# LilyPixel.net
KiCad netlist of a schematic drawn in EAGLE
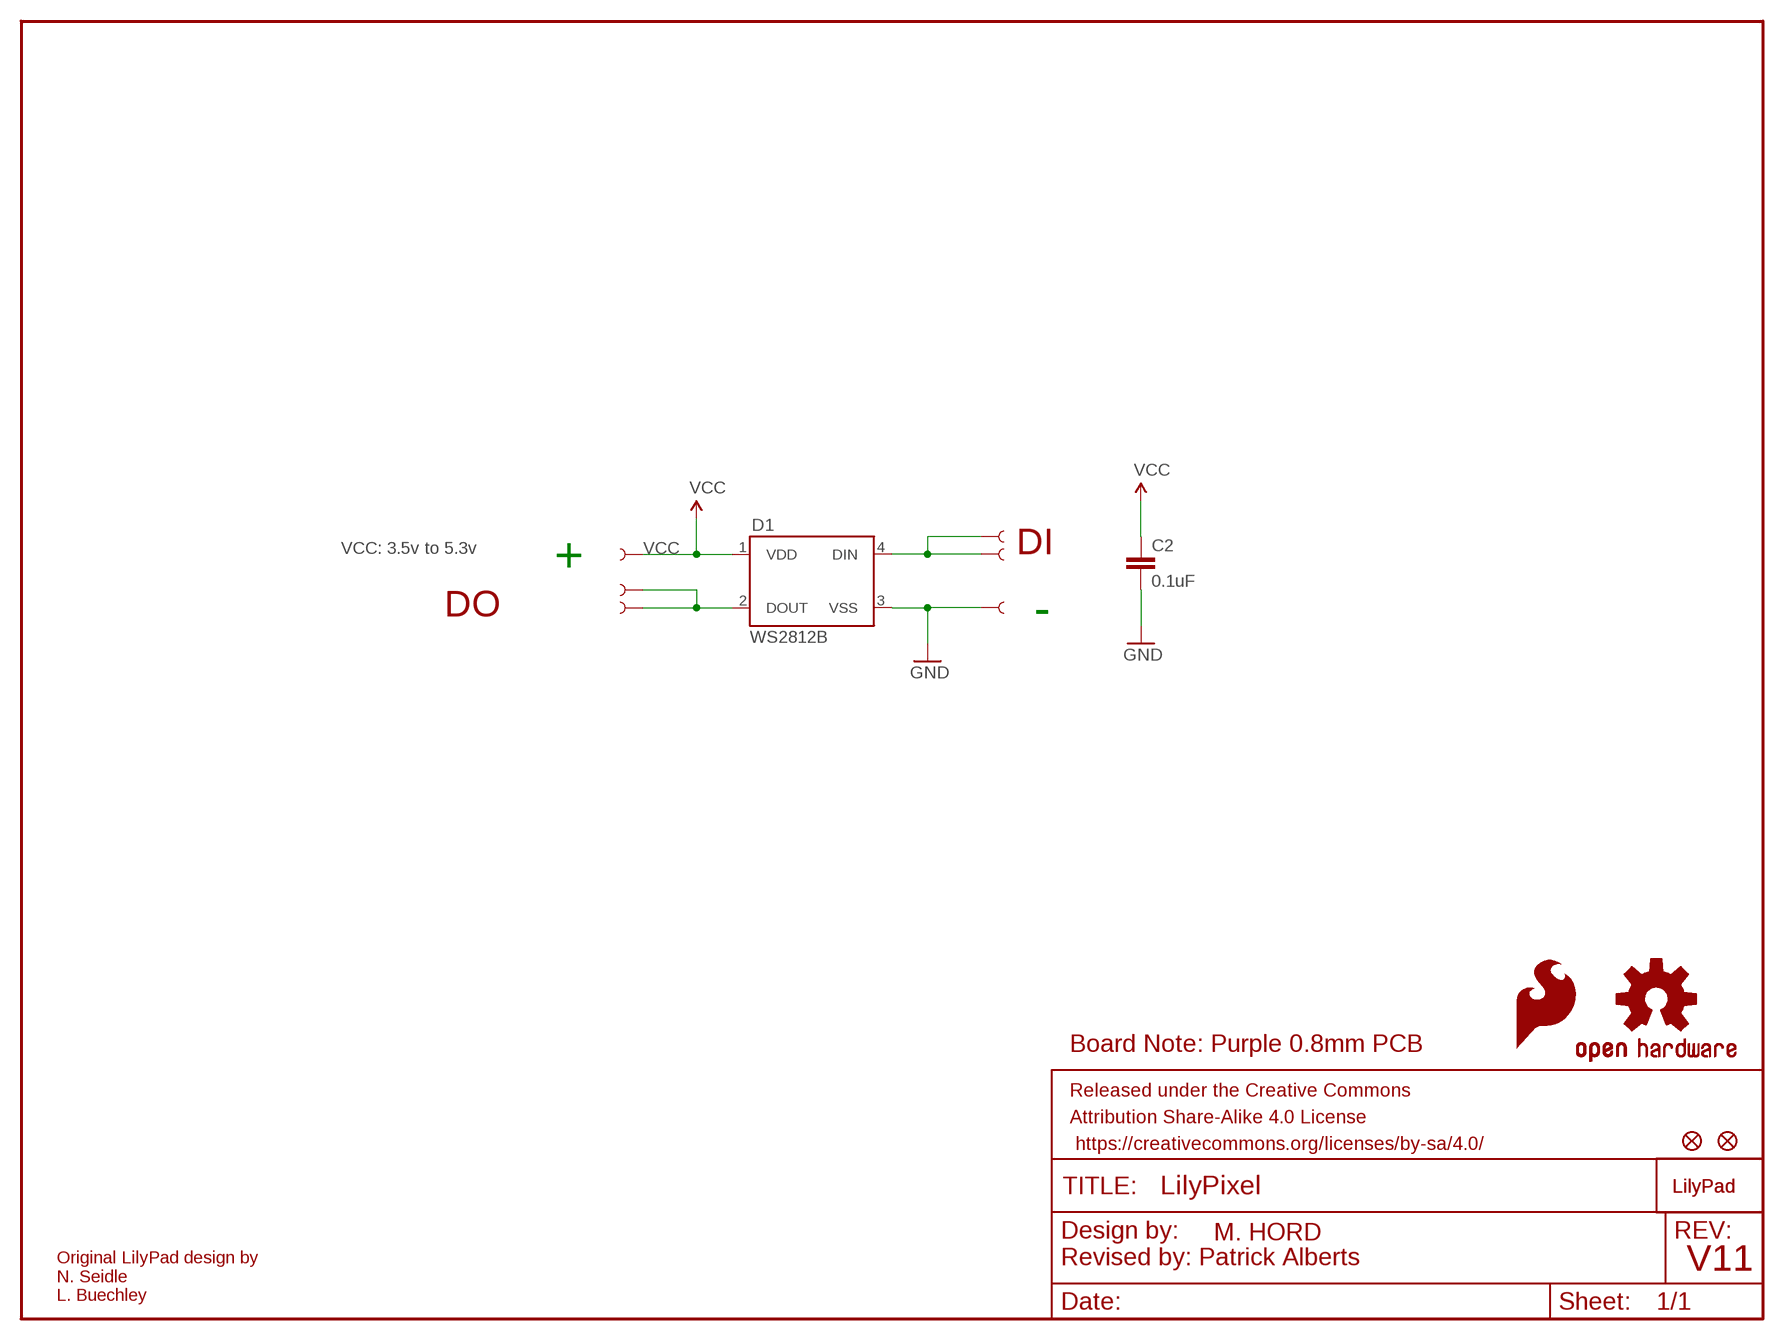
[diagram p0: schematic, sheet 1]

(export (version "E")
  (design (tool "Eeschema 10.0.6"))
  (components
    (comp (ref "C2")
      (value "0.1uF")
      (footprint "eagle-import:0603-CAP")
      (libsource (lib "eagle-import") (part "0.1UF-25V(+80/-20%)(0603)"))
    )
    (comp (ref "D1")
      (value "WS2812B")
      (footprint "eagle-import:WS2812B")
      (libsource (lib "eagle-import") (part "WS2812B"))
    )
    (comp (ref "FID1")
      (value "FIDUCIALUFIDUCIAL")
      (footprint "eagle-import:MICRO-FIDUCIAL")
      (libsource (lib "eagle-import") (part "FIDUCIALUFIDUCIAL"))
    )
    (comp (ref "FID2")
      (value "FIDUCIALUFIDUCIAL")
      (footprint "eagle-import:MICRO-FIDUCIAL")
      (libsource (lib "eagle-import") (part "FIDUCIALUFIDUCIAL"))
    )
    (comp (ref "FRAME1")
      (value "FRAME-LETTER")
      (footprint "eagle-import:CREATIVE_COMMONS")
      (libsource (lib "eagle-import") (part "FRAME-LETTER"))
    )
    (comp (ref "JP1")
      (value "SEWTAP6")
      (footprint "eagle-import:PETAL-SMALL-2SIDE")
      (libsource (lib "eagle-import") (part "SEWTAP6"))
    )
    (comp (ref "JP2")
      (value "SEWTAP6")
      (footprint "eagle-import:PETAL-SMALL-2SIDE")
      (libsource (lib "eagle-import") (part "SEWTAP6"))
    )
    (comp (ref "JP3")
      (value "SEWTAP6")
      (footprint "eagle-import:PETAL-SMALL-2SIDE")
      (libsource (lib "eagle-import") (part "SEWTAP6"))
    )
    (comp (ref "JP4")
      (value "SEWTAP6")
      (footprint "eagle-import:PETAL-SMALL-2SIDE")
      (libsource (lib "eagle-import") (part "SEWTAP6"))
    )
    (comp (ref "JP5")
      (value "SEWTAP6")
      (footprint "eagle-import:PETAL-SMALL-2SIDE")
      (libsource (lib "eagle-import") (part "SEWTAP6"))
    )
    (comp (ref "JP6")
      (value "SEWTAP6")
      (footprint "eagle-import:PETAL-SMALL-2SIDE")
      (libsource (lib "eagle-import") (part "SEWTAP6"))
    )
    (comp (ref "LOGO1")
      (value "OSHW-LOGOS")
      (footprint "eagle-import:OSHW-LOGO-S")
      (libsource (lib "eagle-import") (part "OSHW-LOGOS"))
    )
    (comp (ref "LOGO2")
      (value "SFE_LOGO_FLAME.1_INCH")
      (footprint "eagle-import:SFE_LOGO_FLAME_.1")
      (libsource (lib "eagle-import") (part "SFE_LOGO_FLAME.1_INCH"))
    )
    (comp (ref "U$1")
      (value "LOGO-LPLP")
      (footprint "eagle-import:LOGO-LILYPAD")
      (libsource (lib "eagle-import") (part "LOGO-LPLP"))
    )
    (comp (ref "U$8")
      (value "LOGO-LPL")
      (footprint "eagle-import:LOGO-L")
      (libsource (lib "eagle-import") (part "LOGO-LPL"))
    )
  )
  (nets
    (net (code "1") (name "GND") (class "Default")
      (node (ref "C2") (pin "2") (pinfunction "2_2") (pintype "passive"))
      (node (ref "D1") (pin "3") (pinfunction "VSS_3") (pintype "power_in"))
      (node (ref "JP3") (pin "1") (pinfunction "1_1") (pintype "bidirectional"))
    )
    (net (code "2") (name "Net-(D1-DIN)") (class "Default")
      (node (ref "D1") (pin "4") (pinfunction "DIN_4") (pintype "input"))
      (node (ref "JP5") (pin "1") (pinfunction "1_1") (pintype "bidirectional"))
      (node (ref "JP6") (pin "1") (pinfunction "1_1") (pintype "bidirectional"))
    )
    (net (code "3") (name "Net-(D1-DOUT)") (class "Default")
      (node (ref "D1") (pin "2") (pinfunction "DOUT_2") (pintype "output"))
      (node (ref "JP1") (pin "1") (pinfunction "1_1") (pintype "bidirectional"))
      (node (ref "JP2") (pin "1") (pinfunction "1_1") (pintype "bidirectional"))
    )
    (net (code "4") (name "VCC") (class "Default")
      (node (ref "C2") (pin "1") (pinfunction "1_1") (pintype "passive"))
      (node (ref "D1") (pin "1") (pinfunction "VDD_1") (pintype "power_in"))
      (node (ref "JP4") (pin "1") (pinfunction "1_1") (pintype "bidirectional"))
    )
  )
)
